# LCD_LED_Controls.net
KiCad netlist of a schematic drawn in Altium Designer
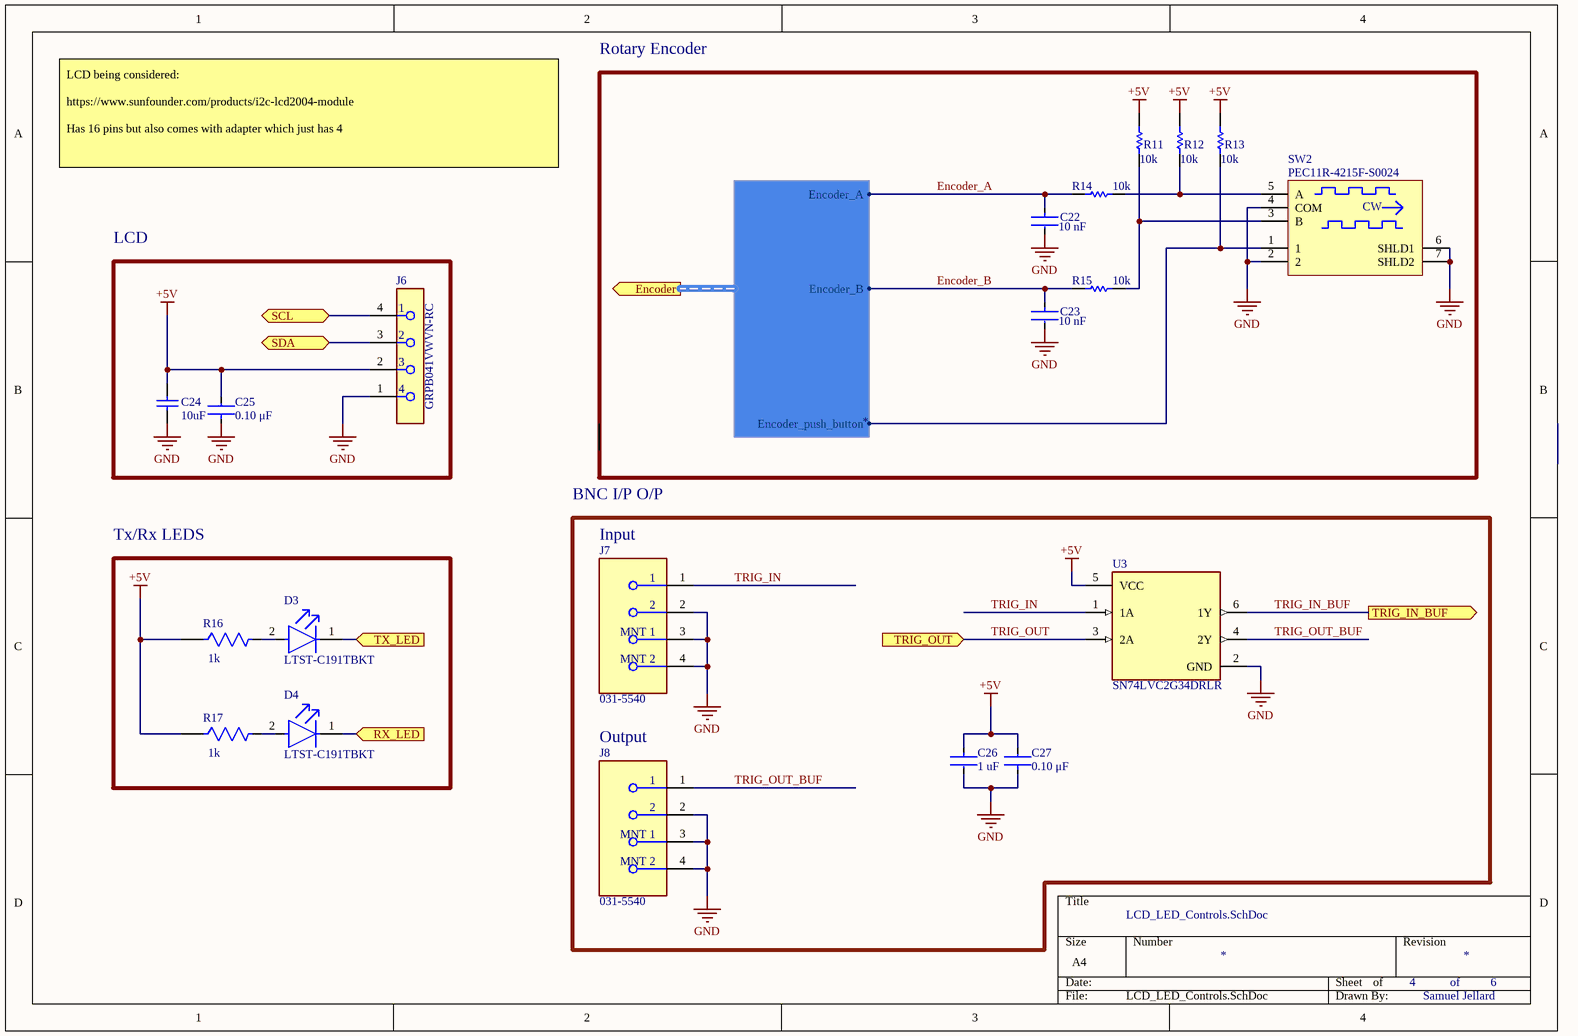
[diagram p0: LCD_LED_Controls.SchDoc]

(export (version "E")
  (design (tool "Eeschema 10.0.6"))
  (components
    (comp (ref "C22")
      (value "10 nF")
      (footprint "FP-CC0603-DA-MFG")
      (description "Surface Mount Ceramic Multilayer Capacitor 0.01uF 10% X7R 25V 0603 Paper T/R")
      (fields (field (name "TOLERANCE") "0.1") (field (name "MANUFACTURER") "YAGEO"))
      (libsource (lib "Altium Content Vault") (part "11868f565c42a9108669ba33697ecf6"))
    )
    (comp (ref "C23")
      (value "10 nF")
      (footprint "FP-CC0603-DA-MFG")
      (description "Surface Mount Ceramic Multilayer Capacitor 0.01uF 10% X7R 25V 0603 Paper T/R")
      (fields (field (name "TOLERANCE") "0.1") (field (name "MANUFACTURER") "YAGEO"))
      (libsource (lib "Altium Content Vault") (part "11868f565c42a9108669ba33697ecf6"))
    )
    (comp (ref "C24")
      (value "10uF")
      (footprint "CAPC0603(1608)100_N")
      (description "CAP 10uF 6.3V ±20% 0603 (1608 Metric) Thickness 1mm SMD")
      (fields (field (name "TOLERANCE") "Â±20%") (field (name "Comment") "C0603C106M9PACTU"))
      (libsource (lib "Altium Content Vault") (part "CAP"))
    )
    (comp (ref "C25")
      (value "0.10 μF")
      (footprint "FP-C0603C-CF-MFG")
      (description "Multilayer Ceramic Capacitors (MLCC) - SMD/SMT 50volts 0.1uF X7R 10%")
      (fields (field (name "TOLERANCE") "0.1") (field (name "MANUFACTURER") "KEMET"))
      (libsource (lib "Altium Content Vault") (part "b4654b650e69147ec39a6b967a45e02"))
    )
    (comp (ref "C26")
      (value "1 uF")
      (footprint "FP-CC0603-DA-MFG")
      (description "0603 1 uF 16 V ±10 % Tolerance X7R SMT Multilayer Ceramic Capacitor")
      (fields (field (name "TOLERANCE") "0.1") (field (name "MANUFACTURER") "YAGEO"))
      (libsource (lib "Altium Content Vault") (part "11868f565c42a9108669ba33697ecf6"))
    )
    (comp (ref "C27")
      (value "0.10 μF")
      (footprint "FP-C0603C-CF-MFG")
      (description "Multilayer Ceramic Capacitors (MLCC) - SMD/SMT 50volts 0.1uF X7R 10%")
      (fields (field (name "TOLERANCE") "0.1") (field (name "MANUFACTURER") "KEMET"))
      (libsource (lib "Altium Content Vault") (part "b4654b650e69147ec39a6b967a45e02"))
    )
    (comp (ref "D3")
      (value "LTST-C191TBKT")
      (footprint "FP-LTST-C191TBKT-MFG")
      (description "LED Uni-Color Blue 468nm 2-Pin Chip LED T/R / LED BLUE CLEAR 0603 SMD")
      (libsource (lib "Altium Content Vault") (part "8706943c75ba83719d021d2fdc84c58"))
    )
    (comp (ref "D4")
      (value "LTST-C191TBKT")
      (footprint "FP-LTST-C191TBKT-MFG")
      (description "LED Uni-Color Blue 468nm 2-Pin Chip LED T/R / LED BLUE CLEAR 0603 SMD")
      (libsource (lib "Altium Content Vault") (part "8706943c75ba83719d021d2fdc84c58"))
    )
    (comp (ref "J6")
      (value "GRPB041VWVN-RC")
      (footprint "LCD2004 footprint:LCD2004")
      (description "CONN HEADER VERT 4POS 1.27MM")
      (libsource (lib "LCD2004 library") (part "56792406a6bd5c25e158f553ecd1aa7"))
    )
    (comp (ref "J7")
      (value "031-5540")
      (footprint "FP-031-5540-MFG")
      (description "CONN BNC RCPT R/A 50 OHM PCB")
      (fields
        (field (name "OCTOPART") "https://octopart.com/031-5540-amphenol+rf-49742301")
        (field (name "MANUFACTURER") "Amphenol RF")
      )
      (libsource (lib "Altium Content Vault") (part "c4223d6e67c9a5a609df11ee682ef75"))
    )
    (comp (ref "J8")
      (value "031-5540")
      (footprint "FP-031-5540-MFG")
      (description "CONN BNC RCPT R/A 50 OHM PCB")
      (fields
        (field (name "OCTOPART") "https://octopart.com/031-5540-amphenol+rf-49742301")
        (field (name "MANUFACTURER") "Amphenol RF")
      )
      (libsource (lib "Altium Content Vault") (part "c4223d6e67c9a5a609df11ee682ef75"))
    )
    (comp (ref "R11")
      (value "CRCW060310K0FKEA")
      (footprint "RESC1609X50X30NL8T20")
      (description "Chip Resistor, 10 KOhm, +/- 1%, 100 mW, -55 to 155 degC, 0603 (1608 Metric), RoHS, Tape and Reel")
      (fields (field (name "MANUFACTURER") "Vishay Semiconductor"))
      (libsource (lib "Altium Content Vault") (part "RES-2"))
    )
    (comp (ref "R12")
      (value "CRCW060310K0FKEA")
      (footprint "RESC1609X50X30NL8T20")
      (description "Chip Resistor, 10 KOhm, +/- 1%, 100 mW, -55 to 155 degC, 0603 (1608 Metric), RoHS, Tape and Reel")
      (fields (field (name "MANUFACTURER") "Vishay Semiconductor"))
      (libsource (lib "Altium Content Vault") (part "RES-2"))
    )
    (comp (ref "R13")
      (value "CRCW060310K0FKEA")
      (footprint "RESC1609X50X30NL8T20")
      (description "Chip Resistor, 10 KOhm, +/- 1%, 100 mW, -55 to 155 degC, 0603 (1608 Metric), RoHS, Tape and Reel")
      (fields (field (name "MANUFACTURER") "Vishay Semiconductor"))
      (libsource (lib "Altium Content Vault") (part "RES-2"))
    )
    (comp (ref "R14")
      (value "CRCW060310K0FKEA")
      (footprint "RESC1609X50X30NL8T20")
      (description "Chip Resistor, 10 KOhm, +/- 1%, 100 mW, -55 to 155 degC, 0603 (1608 Metric), RoHS, Tape and Reel")
      (fields (field (name "MANUFACTURER") "Vishay Semiconductor"))
      (libsource (lib "Altium Content Vault") (part "RES-2"))
    )
    (comp (ref "R15")
      (value "CRCW060310K0FKEA")
      (footprint "RESC1609X50X30NL8T20")
      (description "Chip Resistor, 10 KOhm, +/- 1%, 100 mW, -55 to 155 degC, 0603 (1608 Metric), RoHS, Tape and Reel")
      (fields (field (name "MANUFACTURER") "Vishay Semiconductor"))
      (libsource (lib "Altium Content Vault") (part "RES-2"))
    )
    (comp (ref "R16")
      (value "CRCW06031K00FKEA")
      (footprint "FP-CRCW0603-e3-MFG")
      (description "RES Thick Film, 1kΩ, 1%, 0.1W, 100ppm/°C, 0603")
      (fields (field (name "TOLERANCE") "1%") (field (name "RESISTANCE") "1k"))
      (libsource (lib "Altium Content Vault") (part "1029c3af85768c4190bb7ad29bc67b5"))
    )
    (comp (ref "R17")
      (value "CRCW06031K00FKEA")
      (footprint "FP-CRCW0603-e3-MFG")
      (description "RES Thick Film, 1kΩ, 1%, 0.1W, 100ppm/°C, 0603")
      (fields (field (name "TOLERANCE") "1%") (field (name "RESISTANCE") "1k"))
      (libsource (lib "Altium Content Vault") (part "1029c3af85768c4190bb7ad29bc67b5"))
    )
    (comp (ref "SW2")
      (value "PEC11R-4215F-S0024")
      (footprint "BOUR-PEC11R-4XXXF-SXXXX_V")
      (description "12 mm Incremental Encoder, 24 Detent, -30 to 70 degC, 5-Pin THD, RoHS, Bulk")
      (fields (field (name "TOLERANCE") "1%"))
      (libsource (lib "Altium Content Vault") (part "SW-ENCODER-5"))
    )
    (comp (ref "U3")
      (value "SN74LVC2G34DRLR")
      (footprint "FP-DRL0006A-MFG")
      (description "IC BUFFER NON-INVERT 5.5V 6SOT")
      (libsource (lib "Altium Content Vault") (part "59303bce76f5fafbc101ba271662c75"))
    )
  )
  (nets
    (net (code "2") (name "+5V") (class "Default")
      (node (ref "C24") (pin "2") (pinfunction "2_2") (pintype "passive"))
      (node (ref "C25") (pin "2") (pinfunction "2_2") (pintype "passive"))
      (node (ref "C26") (pin "1") (pinfunction "1_1") (pintype "passive"))
      (node (ref "C27") (pin "2") (pinfunction "2_2") (pintype "passive"))
      (node (ref "J6") (pin "2") (pinfunction "2_2") (pintype "passive"))
      (node (ref "R11") (pin "2") (pinfunction "2_2") (pintype "passive"))
      (node (ref "R12") (pin "2") (pinfunction "2_2") (pintype "passive"))
      (node (ref "R13") (pin "2") (pinfunction "2_2") (pintype "passive"))
      (node (ref "R16") (pin "1") (pinfunction "1_1") (pintype "passive"))
      (node (ref "R17") (pin "1") (pinfunction "1_1") (pintype "passive"))
      (node (ref "U3") (pin "5") (pinfunction "VCC_5") (pintype "power_in"))
    )
    (net (code "3") (name "/Encoder_A") (class "Default")
      (node (ref "C22") (pin "1") (pinfunction "1_1") (pintype "passive"))
      (node (ref "R14") (pin "2") (pinfunction "2_2") (pintype "passive"))
    )
    (net (code "4") (name "/Encoder_B") (class "Default")
      (node (ref "C23") (pin "1") (pinfunction "1_1") (pintype "passive"))
      (node (ref "R15") (pin "2") (pinfunction "2_2") (pintype "passive"))
    )
    (net (code "5") (name "/RX_LED") (class "Default")
      (node (ref "D4") (pin "1") (pinfunction "C_1") (pintype "passive"))
    )
    (net (code "6") (name "/SCL") (class "Default")
      (node (ref "J6") (pin "4") (pinfunction "4_4") (pintype "passive"))
    )
    (net (code "7") (name "/SDA") (class "Default")
      (node (ref "J6") (pin "3") (pinfunction "3_3") (pintype "passive"))
    )
    (net (code "8") (name "/TRIG_IN") (class "Default")
      (node (ref "J7") (pin "1") (pinfunction "1_1") (pintype "passive"))
      (node (ref "U3") (pin "1") (pinfunction "1A_1") (pintype "input"))
    )
    (net (code "9") (name "/TRIG_IN_BUF") (class "Default")
      (node (ref "U3") (pin "6") (pinfunction "1Y_6") (pintype "output"))
    )
    (net (code "10") (name "/TRIG_OUT") (class "Default")
      (node (ref "U3") (pin "3") (pinfunction "2A_3") (pintype "input"))
    )
    (net (code "11") (name "/TRIG_OUT_BUF") (class "Default")
      (node (ref "J8") (pin "1") (pinfunction "1_1") (pintype "passive"))
      (node (ref "U3") (pin "4") (pinfunction "2Y_4") (pintype "output"))
    )
    (net (code "12") (name "/TX_LED") (class "Default")
      (node (ref "D3") (pin "1") (pinfunction "C_1") (pintype "passive"))
    )
    (net (code "14") (name "GND") (class "Default")
      (node (ref "C22") (pin "2") (pinfunction "2_2") (pintype "passive"))
      (node (ref "C23") (pin "2") (pinfunction "2_2") (pintype "passive"))
      (node (ref "C24") (pin "1") (pinfunction "1_1") (pintype "passive"))
      (node (ref "C25") (pin "1") (pinfunction "1_1") (pintype "passive"))
      (node (ref "C26") (pin "2") (pinfunction "2_2") (pintype "passive"))
      (node (ref "C27") (pin "1") (pinfunction "1_1") (pintype "passive"))
      (node (ref "J6") (pin "1") (pinfunction "1_1") (pintype "passive"))
      (node (ref "J7") (pin "2") (pinfunction "2_2") (pintype "passive"))
      (node (ref "J7") (pin "3") (pinfunction "MNT_1_3") (pintype "passive"))
      (node (ref "J7") (pin "4") (pinfunction "MNT_2_4") (pintype "passive"))
      (node (ref "J8") (pin "2") (pinfunction "2_2") (pintype "passive"))
      (node (ref "J8") (pin "3") (pinfunction "MNT_1_3") (pintype "passive"))
      (node (ref "J8") (pin "4") (pinfunction "MNT_2_4") (pintype "passive"))
      (node (ref "SW2") (pin "2") (pinfunction "2_2") (pintype "passive"))
      (node (ref "SW2") (pin "4") (pinfunction "COM_4") (pintype "passive"))
      (node (ref "SW2") (pin "6") (pinfunction "SHLD1_6") (pintype "passive"))
      (node (ref "SW2") (pin "7") (pinfunction "SHLD2_7") (pintype "passive"))
      (node (ref "U3") (pin "2") (pinfunction "GND_2") (pintype "power_in"))
    )
    (net (code "15") (name "Net-(D3-A)") (class "Default")
      (node (ref "D3") (pin "2") (pinfunction "A_2") (pintype "passive"))
      (node (ref "R16") (pin "2") (pinfunction "2_2") (pintype "passive"))
    )
    (net (code "16") (name "Net-(D4-A)") (class "Default")
      (node (ref "D4") (pin "2") (pinfunction "A_2") (pintype "passive"))
      (node (ref "R17") (pin "2") (pinfunction "2_2") (pintype "passive"))
    )
    (net (code "17") (name "Net-(R13-Pad1)") (class "Default")
      (node (ref "R13") (pin "1") (pinfunction "1_1") (pintype "passive"))
      (node (ref "SW2") (pin "1") (pinfunction "1_1") (pintype "passive"))
    )
    (net (code "18") (name "Net-(SW2-A)") (class "Default")
      (node (ref "R12") (pin "1") (pinfunction "1_1") (pintype "passive"))
      (node (ref "R14") (pin "1") (pinfunction "1_1") (pintype "passive"))
      (node (ref "SW2") (pin "5") (pinfunction "A_5") (pintype "passive"))
    )
    (net (code "19") (name "Net-(SW2-B)") (class "Default")
      (node (ref "R11") (pin "1") (pinfunction "1_1") (pintype "passive"))
      (node (ref "R15") (pin "1") (pinfunction "1_1") (pintype "passive"))
      (node (ref "SW2") (pin "3") (pinfunction "B_3") (pintype "passive"))
    )
  )
)
